# SCH_STM32_V3_3_0_2023-02-14.net
KiCad netlist of a schematic drawn in EasyEDA
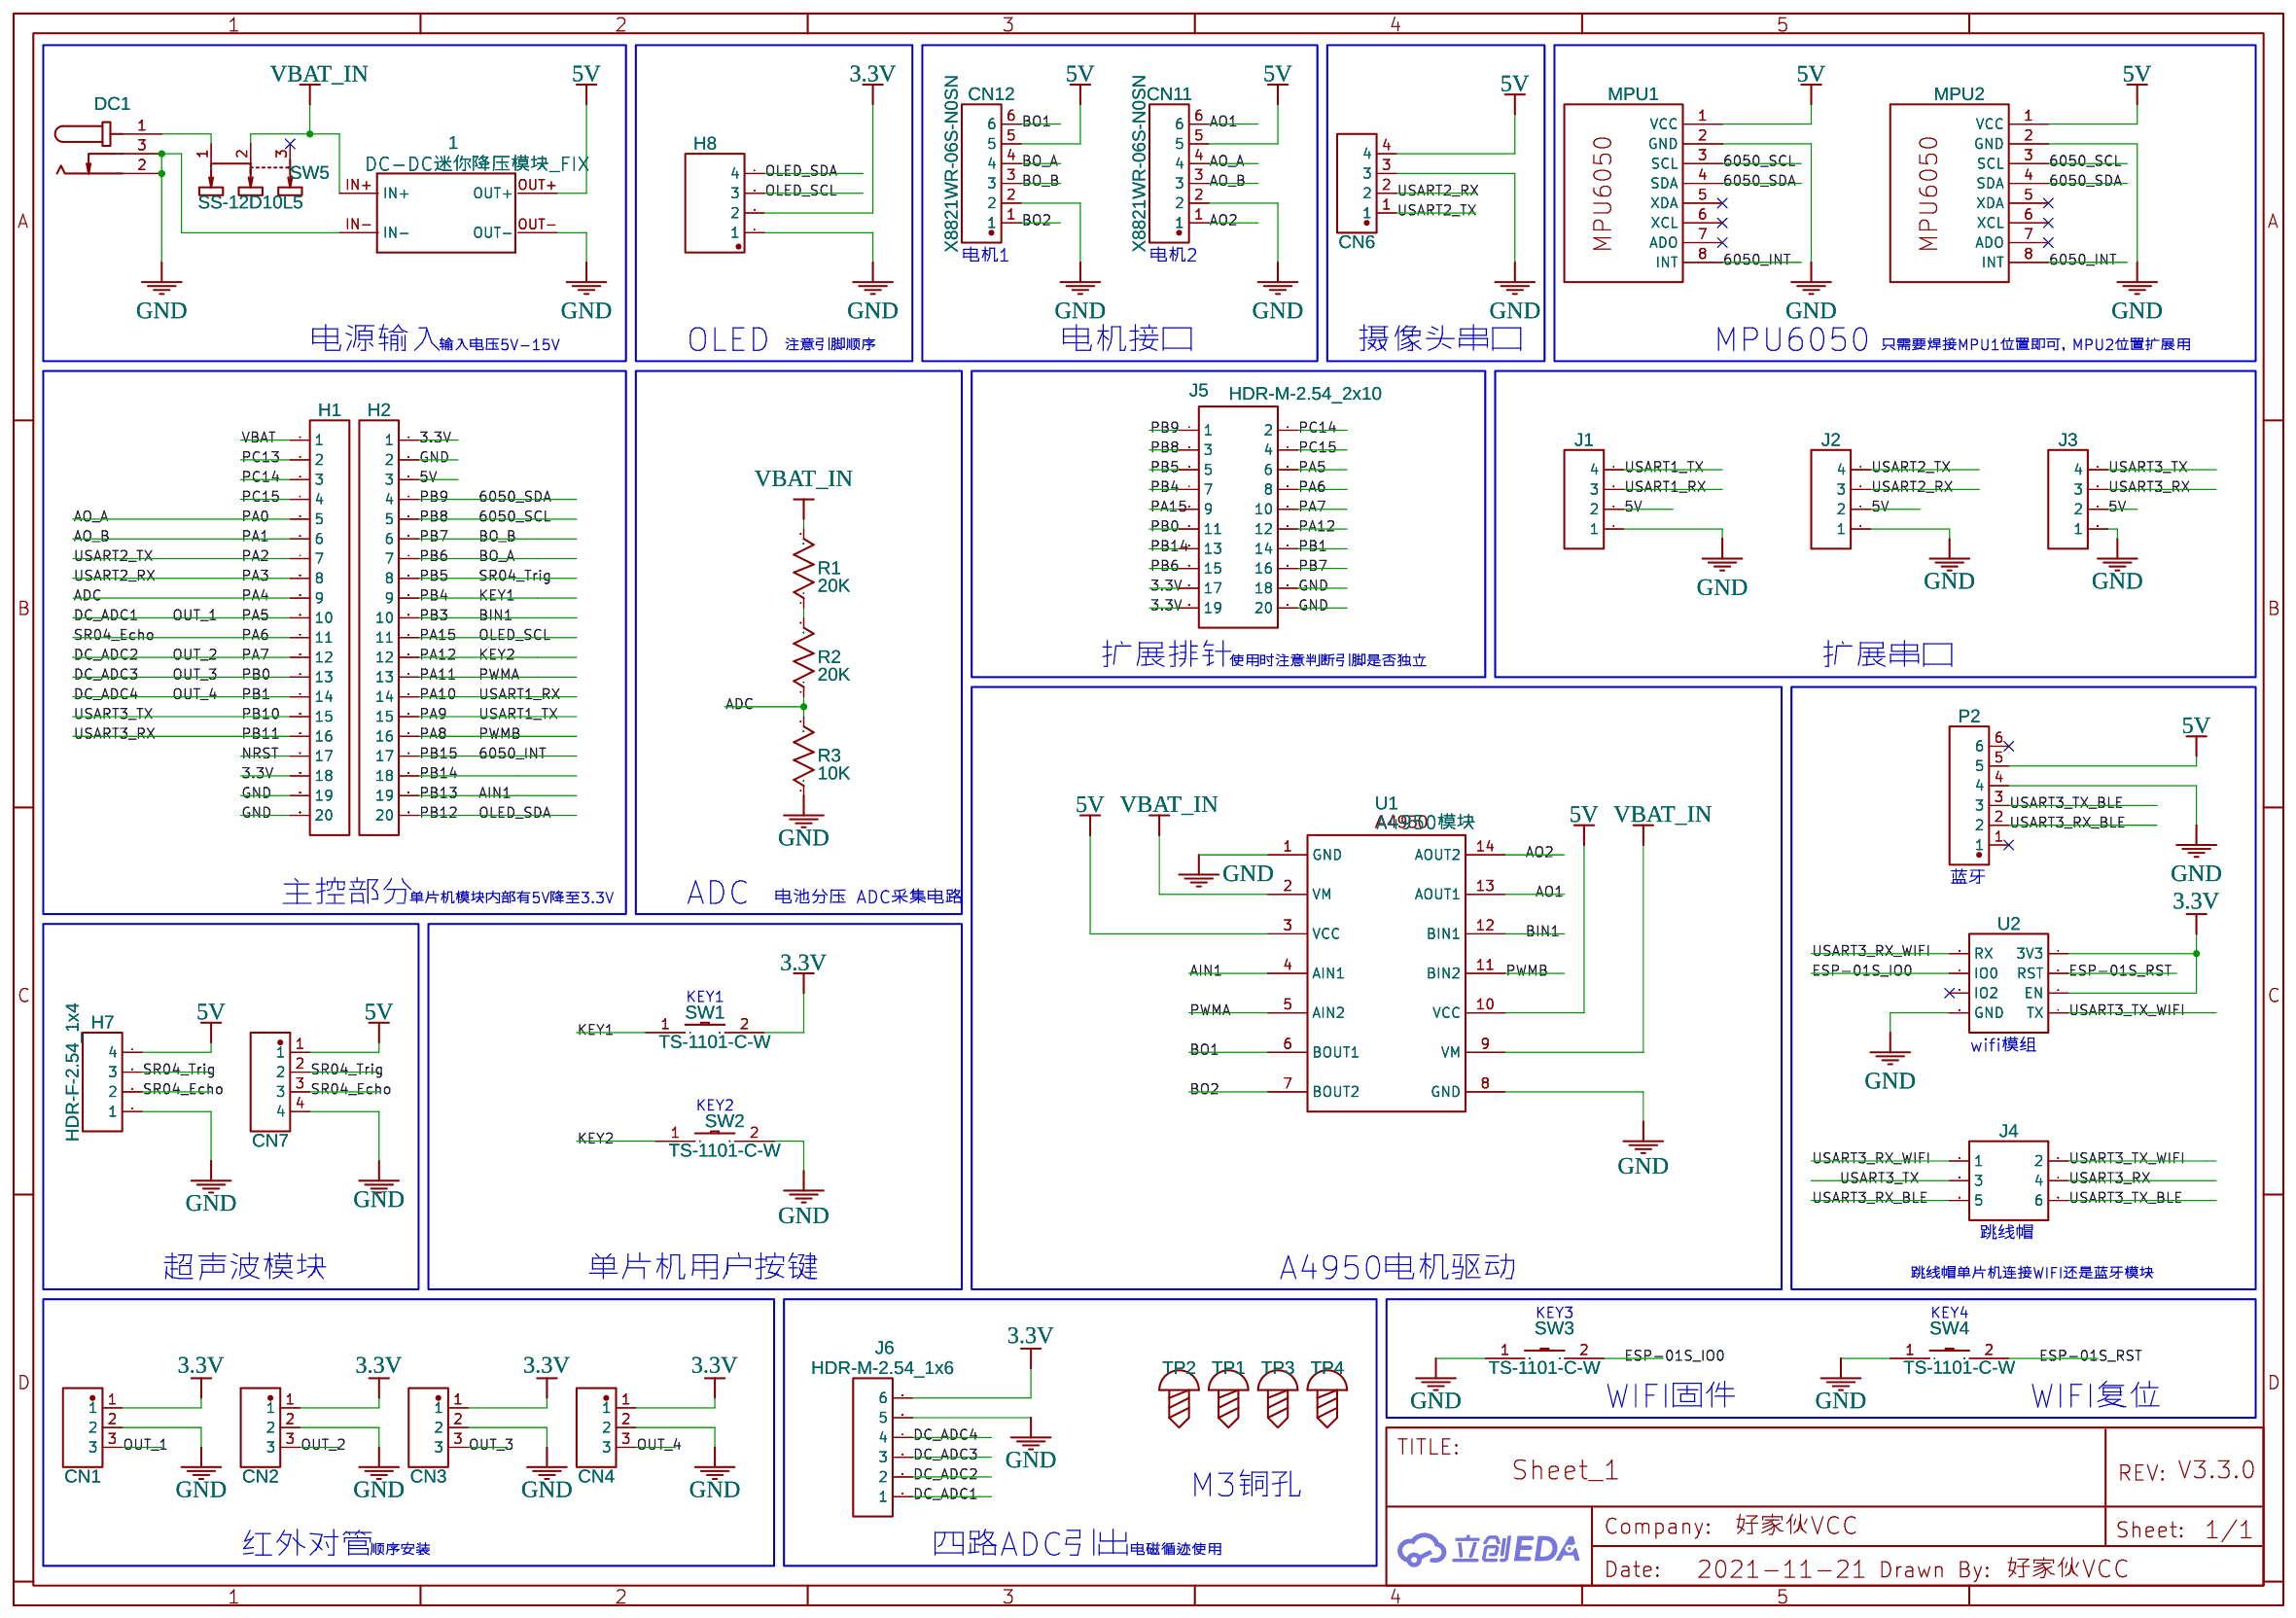
[diagram p0: schematic sheet]

(export (version "E")
  (design (tool "Eeschema 10.0.6"))
  (components
    (comp (ref "1") (value "DC-DC迷你降压模块_FIX") (libsource (lib "") (part "DC-DC迷你降压模块_FIX")))
    (comp (ref "CN1")
      (value "X8821WR-03S-N0SN")
      (fields (field (name "BOM_Supplier Part") "C388740"))
      (libsource (lib "") (part "X8821WR-03S-N0SN"))
    )
    (comp (ref "CN2")
      (value "X8821WR-03S-N0SN")
      (fields (field (name "BOM_Supplier Part") "C388740"))
      (libsource (lib "") (part "X8821WR-03S-N0SN"))
    )
    (comp (ref "CN3")
      (value "X8821WR-03S-N0SN")
      (fields (field (name "BOM_Supplier Part") "C388740"))
      (libsource (lib "") (part "X8821WR-03S-N0SN"))
    )
    (comp (ref "CN4")
      (value "X8821WR-03S-N0SN")
      (fields (field (name "BOM_Supplier Part") "C388740"))
      (libsource (lib "") (part "X8821WR-03S-N0SN"))
    )
    (comp (ref "CN6")
      (value "HX25003-4WAP")
      (fields (field (name "BOM_Supplier Part") "C442328"))
      (libsource (lib "") (part "HX25003-4WAP_1"))
    )
    (comp (ref "CN7")
      (value "HX25003-4WAP")
      (fields (field (name "BOM_Supplier Part") "C442328"))
      (libsource (lib "") (part "HX25003-4WAP"))
    )
    (comp (ref "CN11")
      (value "X8821WR-06S-N0SN")
      (fields (field (name "BOM_Supplier Part") "C388743"))
      (libsource (lib "") (part "X8821WR-06S-N0SN"))
    )
    (comp (ref "CN12")
      (value "X8821WR-06S-N0SN")
      (fields (field (name "BOM_Supplier Part") "C388743"))
      (libsource (lib "") (part "X8821WR-06S-N0SN"))
    )
    (comp (ref "DC1")
      (value "DC005_C431533")
      (fields (field (name "BOM_Manufacturer Part") "DC005") (field (name "BOM_Supplier Part") "C431533"))
      (libsource (lib "") (part "DC005_C431533"))
    )
    (comp (ref "H1")
      (value "HDR-F-2.54_1x20")
      (fields
        (field (name "BOM_Manufacturer Part") "2.54mm 1*20P Female header")
        (field (name "BOM_Supplier Part") "C50984")
      )
      (libsource (lib "") (part "HDR-F-2.54_1x20_1"))
    )
    (comp (ref "H2")
      (value "HDR-F-2.54_1x20")
      (fields
        (field (name "BOM_Manufacturer Part") "2.54mm 1*20P Female header")
        (field (name "BOM_Supplier Part") "C50984")
      )
      (libsource (lib "") (part "HDR-F-2.54_1x20"))
    )
    (comp (ref "H7")
      (value "HDR-F-2.54_1x4")
      (fields (field (name "BOM_Supplier Part") "C225501"))
      (libsource (lib "") (part "HDR-F-2.54_1x4"))
    )
    (comp (ref "H8")
      (value "Header-Male-2.54_1x4")
      (fields
        (field (name "BOM_Manufacturer Part") "A2541HWV-4P")
        (field (name "BOM_Supplier Part") "C225501")
      )
      (libsource (lib "") (part "Header-Male-2.54_1x4"))
    )
    (comp (ref "J1")
      (value "HDR-M-2.54_1x4")
      (fields (field (name "BOM_Supplier Part") "C124378"))
      (libsource (lib "") (part "HDR-M-2.54_1x4"))
    )
    (comp (ref "J2")
      (value "HDR-M-2.54_1x4")
      (fields (field (name "BOM_Supplier Part") "C124378"))
      (libsource (lib "") (part "HDR-M-2.54_1x4"))
    )
    (comp (ref "J3")
      (value "HDR-M-2.54_1x4")
      (fields (field (name "BOM_Supplier Part") "C124378"))
      (libsource (lib "") (part "HDR-M-2.54_1x4"))
    )
    (comp (ref "J4")
      (value "Header-Male-2.54_2x3")
      (fields (field (name "BOM_Supplier Part") "C65114"))
      (libsource (lib "") (part "Header-Male-2.54_2x3"))
    )
    (comp (ref "J5")
      (value "HDR-M-2.54_2x10")
      (fields (field (name "BOM_Supplier Part") "C124359"))
      (libsource (lib "") (part "HDR-M-2.54_2x10"))
    )
    (comp (ref "J6")
      (value "HDR-M-2.54_1x6")
      (fields (field (name "BOM_Supplier Part") "C190819"))
      (libsource (lib "") (part "HDR-M-2.54_1x6"))
    )
    (comp (ref "MPU1") (value "MPU6050 有孔(锁定丝印)") (libsource (lib "") (part "MPU6050 有孔(锁定丝印)")))
    (comp (ref "MPU2") (value "MPU6050 有孔(锁定丝印)") (libsource (lib "") (part "MPU6050 有孔(锁定丝印)")))
    (comp (ref "P2")
      (value "Header-Female-2.54_1x6")
      (fields
        (field (name "BOM_Manufacturer Part") "Female header 1*6p")
        (field (name "BOM_Supplier Part") "C40877")
      )
      (libsource (lib "") (part "Header-Female-2.54_1x6"))
    )
    (comp (ref "R1") (value "20K") (libsource (lib "") (part "R_0603_US")))
    (comp (ref "R2") (value "20K") (libsource (lib "") (part "R_0603_US")))
    (comp (ref "R3") (value "10K") (libsource (lib "") (part "R_0603_US")))
    (comp (ref "SW1")
      (value "TS-1101-C-W")
      (fields (field (name "BOM_Supplier Part") "C318938"))
      (libsource (lib "") (part "TS-1101-C-W"))
    )
    (comp (ref "SW2")
      (value "TS-1101-C-W")
      (fields (field (name "BOM_Supplier Part") "C318938"))
      (libsource (lib "") (part "TS-1101-C-W"))
    )
    (comp (ref "SW3")
      (value "TS-1101-C-W")
      (fields (field (name "BOM_Supplier Part") "C318938"))
      (libsource (lib "") (part "TS-1101-C-W"))
    )
    (comp (ref "SW4")
      (value "TS-1101-C-W")
      (fields (field (name "BOM_Supplier Part") "C318938"))
      (libsource (lib "") (part "TS-1101-C-W"))
    )
    (comp (ref "SW5")
      (value "SS-12D10L5")
      (fields (field (name "BOM_Supplier Part") "C319012"))
      (libsource (lib "") (part "SS-12D10L5"))
    )
    (comp (ref "TP1") (value "M3铜柱带丝印") (libsource (lib "") (part "M3铜柱带丝印")))
    (comp (ref "TP2") (value "M3铜柱带丝印") (libsource (lib "") (part "M3铜柱带丝印")))
    (comp (ref "TP3") (value "M3铜柱带丝印") (libsource (lib "") (part "M3铜柱带丝印")))
    (comp (ref "TP4") (value "M3铜柱带丝印") (libsource (lib "") (part "M3铜柱带丝印")))
    (comp (ref "U1") (value "A4950模块") (libsource (lib "") (part "A4950模块")))
    (comp (ref "U2") (value "ESP-01S模块") (libsource (lib "") (part "ESP-01S模块")))
  )
  (nets
    (net (code "1") (name "/6050_INT") (class "Default")
      (node (ref "H2") (pin "17") (pinfunction "17_17") (pintype "unspecified"))
      (node (ref "MPU1") (pin "8") (pinfunction "INT_8") (pintype "unspecified"))
      (node (ref "MPU2") (pin "8") (pinfunction "INT_8") (pintype "unspecified"))
    )
    (net (code "2") (name "/6050_SCL") (class "Default")
      (node (ref "H2") (pin "5") (pinfunction "5_5") (pintype "unspecified"))
      (node (ref "J5") (pin "3") (pinfunction "3_3") (pintype "unspecified"))
      (node (ref "MPU1") (pin "3") (pinfunction "SCL_3") (pintype "unspecified"))
      (node (ref "MPU2") (pin "3") (pinfunction "SCL_3") (pintype "unspecified"))
    )
    (net (code "3") (name "/6050_SDA") (class "Default")
      (node (ref "H2") (pin "4") (pinfunction "4_4") (pintype "unspecified"))
      (node (ref "J5") (pin "1") (pinfunction "1_1") (pintype "unspecified"))
      (node (ref "MPU1") (pin "4") (pinfunction "SDA_4") (pintype "unspecified"))
      (node (ref "MPU2") (pin "4") (pinfunction "SDA_4") (pintype "unspecified"))
    )
    (net (code "4") (name "/ADC") (class "Default")
      (node (ref "H1") (pin "9") (pinfunction "9_9") (pintype "unspecified"))
      (node (ref "R2") (pin "1") (pinfunction "1_1") (pintype "unspecified"))
      (node (ref "R3") (pin "2") (pinfunction "2_2") (pintype "unspecified"))
    )
    (net (code "5") (name "/AIN1") (class "Default")
      (node (ref "H2") (pin "19") (pinfunction "19_19") (pintype "unspecified"))
      (node (ref "U1") (pin "4") (pinfunction "AIN1_4") (pintype "unspecified"))
    )
    (net (code "6") (name "/AO1") (class "Default")
      (node (ref "CN11") (pin "6") (pinfunction "6_6") (pintype "unspecified"))
      (node (ref "U1") (pin "13") (pinfunction "AOUT1_13") (pintype "unspecified"))
    )
    (net (code "7") (name "/AO2") (class "Default")
      (node (ref "CN11") (pin "1") (pinfunction "1_1") (pintype "unspecified"))
      (node (ref "U1") (pin "14") (pinfunction "AOUT2_14") (pintype "unspecified"))
    )
    (net (code "8") (name "/AO_A") (class "Default")
      (node (ref "CN11") (pin "4") (pinfunction "4_4") (pintype "unspecified"))
      (node (ref "H1") (pin "5") (pinfunction "5_5") (pintype "unspecified"))
    )
    (net (code "9") (name "/AO_B") (class "Default")
      (node (ref "CN11") (pin "3") (pinfunction "3_3") (pintype "unspecified"))
      (node (ref "H1") (pin "6") (pinfunction "6_6") (pintype "unspecified"))
    )
    (net (code "10") (name "/BIN1") (class "Default")
      (node (ref "H2") (pin "10") (pinfunction "10_10") (pintype "unspecified"))
      (node (ref "U1") (pin "12") (pinfunction "BIN1_12") (pintype "unspecified"))
    )
    (net (code "11") (name "/BO1") (class "Default")
      (node (ref "CN12") (pin "6") (pinfunction "6_6") (pintype "unspecified"))
      (node (ref "U1") (pin "6") (pinfunction "BOUT1_6") (pintype "unspecified"))
    )
    (net (code "12") (name "/BO2") (class "Default")
      (node (ref "CN12") (pin "1") (pinfunction "1_1") (pintype "unspecified"))
      (node (ref "U1") (pin "7") (pinfunction "BOUT2_7") (pintype "unspecified"))
    )
    (net (code "13") (name "/BO_A") (class "Default")
      (node (ref "CN12") (pin "4") (pinfunction "4_4") (pintype "unspecified"))
      (node (ref "H2") (pin "7") (pinfunction "7_7") (pintype "unspecified"))
      (node (ref "J5") (pin "15") (pinfunction "15_15") (pintype "unspecified"))
    )
    (net (code "14") (name "/BO_B") (class "Default")
      (node (ref "CN12") (pin "3") (pinfunction "3_3") (pintype "unspecified"))
      (node (ref "H2") (pin "6") (pinfunction "6_6") (pintype "unspecified"))
      (node (ref "J5") (pin "16") (pinfunction "16_16") (pintype "unspecified"))
    )
    (net (code "15") (name "/DC_ADC1") (class "Default")
      (node (ref "CN1") (pin "3") (pinfunction "3_3") (pintype "unspecified"))
      (node (ref "H1") (pin "10") (pinfunction "10_10") (pintype "unspecified"))
      (node (ref "J5") (pin "6") (pinfunction "6_6") (pintype "unspecified"))
      (node (ref "J6") (pin "1") (pinfunction "1_1") (pintype "input"))
    )
    (net (code "16") (name "/DC_ADC2") (class "Default")
      (node (ref "CN2") (pin "3") (pinfunction "3_3") (pintype "unspecified"))
      (node (ref "H1") (pin "12") (pinfunction "12_12") (pintype "unspecified"))
      (node (ref "J5") (pin "10") (pinfunction "10_10") (pintype "unspecified"))
      (node (ref "J6") (pin "2") (pinfunction "2_2") (pintype "input"))
    )
    (net (code "17") (name "/DC_ADC3") (class "Default")
      (node (ref "CN3") (pin "3") (pinfunction "3_3") (pintype "unspecified"))
      (node (ref "H1") (pin "13") (pinfunction "13_13") (pintype "unspecified"))
      (node (ref "J5") (pin "11") (pinfunction "11_11") (pintype "unspecified"))
      (node (ref "J6") (pin "3") (pinfunction "3_3") (pintype "input"))
    )
    (net (code "18") (name "/DC_ADC4") (class "Default")
      (node (ref "CN4") (pin "3") (pinfunction "3_3") (pintype "unspecified"))
      (node (ref "H1") (pin "14") (pinfunction "14_14") (pintype "unspecified"))
      (node (ref "J5") (pin "14") (pinfunction "14_14") (pintype "unspecified"))
      (node (ref "J6") (pin "4") (pinfunction "4_4") (pintype "input"))
    )
    (net (code "19") (name "/ESP-01S_IO0") (class "Default")
      (node (ref "SW3") (pin "2") (pinfunction "2_2") (pintype "unspecified"))
      (node (ref "U2") (pin "7") (pinfunction "IO0_7") (pintype "unspecified"))
    )
    (net (code "20") (name "/ESP-01S_RST") (class "Default")
      (node (ref "SW4") (pin "2") (pinfunction "2_2") (pintype "unspecified"))
      (node (ref "U2") (pin "2") (pinfunction "RST_2") (pintype "unspecified"))
    )
    (net (code "21") (name "/KEY1") (class "Default")
      (node (ref "H2") (pin "9") (pinfunction "9_9") (pintype "unspecified"))
      (node (ref "J5") (pin "7") (pinfunction "7_7") (pintype "unspecified"))
      (node (ref "SW1") (pin "1") (pinfunction "1_1") (pintype "unspecified"))
    )
    (net (code "22") (name "/KEY2") (class "Default")
      (node (ref "H2") (pin "12") (pinfunction "12_12") (pintype "unspecified"))
      (node (ref "J5") (pin "12") (pinfunction "12_12") (pintype "unspecified"))
      (node (ref "SW2") (pin "1") (pinfunction "1_1") (pintype "unspecified"))
    )
    (net (code "23") (name "/NRST") (class "Default")
      (node (ref "H1") (pin "17") (pinfunction "17_17") (pintype "unspecified"))
    )
    (net (code "24") (name "/OLED_SCL") (class "Default")
      (node (ref "H2") (pin "11") (pinfunction "11_11") (pintype "unspecified"))
      (node (ref "H8") (pin "3") (pinfunction "3_3") (pintype "unspecified"))
      (node (ref "J5") (pin "9") (pinfunction "9_9") (pintype "unspecified"))
    )
    (net (code "25") (name "/OLED_SDA") (class "Default")
      (node (ref "H2") (pin "20") (pinfunction "20_20") (pintype "unspecified"))
      (node (ref "H8") (pin "4") (pinfunction "4_4") (pintype "unspecified"))
    )
    (net (code "26") (name "/PA2") (class "Default")
      (node (ref "CN6") (pin "1") (pinfunction "1_1") (pintype "unspecified"))
      (node (ref "H1") (pin "7") (pinfunction "7_7") (pintype "unspecified"))
      (node (ref "J2") (pin "4") (pinfunction "4_4") (pintype "unspecified"))
    )
    (net (code "27") (name "/PA3") (class "Default")
      (node (ref "CN6") (pin "2") (pinfunction "2_2") (pintype "unspecified"))
      (node (ref "H1") (pin "8") (pinfunction "8_8") (pintype "unspecified"))
      (node (ref "J2") (pin "3") (pinfunction "3_3") (pintype "unspecified"))
    )
    (net (code "28") (name "/PA6") (class "Default")
      (node (ref "CN7") (pin "3") (pinfunction "3_3") (pintype "unspecified"))
      (node (ref "H1") (pin "11") (pinfunction "11_11") (pintype "unspecified"))
      (node (ref "H7") (pin "2") (pinfunction "2_2") (pintype "unspecified"))
      (node (ref "J5") (pin "8") (pinfunction "8_8") (pintype "unspecified"))
    )
    (net (code "29") (name "/PA8") (class "Default")
      (node (ref "H2") (pin "16") (pinfunction "16_16") (pintype "unspecified"))
      (node (ref "U1") (pin "11") (pinfunction "BIN2_11") (pintype "unspecified"))
    )
    (net (code "30") (name "/PA9") (class "Default")
      (node (ref "H2") (pin "15") (pinfunction "15_15") (pintype "unspecified"))
      (node (ref "J1") (pin "4") (pinfunction "4_4") (pintype "unspecified"))
    )
    (net (code "31") (name "/PA10") (class "Default")
      (node (ref "H2") (pin "14") (pinfunction "14_14") (pintype "unspecified"))
      (node (ref "J1") (pin "3") (pinfunction "3_3") (pintype "unspecified"))
    )
    (net (code "32") (name "/PA11") (class "Default")
      (node (ref "H2") (pin "13") (pinfunction "13_13") (pintype "unspecified"))
      (node (ref "U1") (pin "5") (pinfunction "AIN2_5") (pintype "unspecified"))
    )
    (net (code "33") (name "/PB5") (class "Default")
      (node (ref "CN7") (pin "2") (pinfunction "2_2") (pintype "unspecified"))
      (node (ref "H2") (pin "8") (pinfunction "8_8") (pintype "unspecified"))
      (node (ref "H7") (pin "3") (pinfunction "3_3") (pintype "unspecified"))
      (node (ref "J5") (pin "5") (pinfunction "5_5") (pintype "unspecified"))
    )
    (net (code "34") (name "/PB10") (class "Default")
      (node (ref "H1") (pin "15") (pinfunction "15_15") (pintype "unspecified"))
      (node (ref "J3") (pin "4") (pinfunction "4_4") (pintype "unspecified"))
      (node (ref "J4") (pin "3") (pinfunction "3_3") (pintype "input"))
    )
    (net (code "35") (name "/PB11") (class "Default")
      (node (ref "H1") (pin "16") (pinfunction "16_16") (pintype "unspecified"))
      (node (ref "J3") (pin "3") (pinfunction "3_3") (pintype "unspecified"))
      (node (ref "J4") (pin "4") (pinfunction "4_4") (pintype "input"))
    )
    (net (code "36") (name "/PB14") (class "Default")
      (node (ref "H2") (pin "18") (pinfunction "18_18") (pintype "unspecified"))
      (node (ref "J5") (pin "13") (pinfunction "13_13") (pintype "unspecified"))
    )
    (net (code "37") (name "/PC13") (class "Default")
      (node (ref "H1") (pin "2") (pinfunction "2_2") (pintype "unspecified"))
    )
    (net (code "38") (name "/PC14") (class "Default")
      (node (ref "H1") (pin "3") (pinfunction "3_3") (pintype "unspecified"))
      (node (ref "J5") (pin "2") (pinfunction "2_2") (pintype "unspecified"))
    )
    (net (code "39") (name "/PC15") (class "Default")
      (node (ref "H1") (pin "4") (pinfunction "4_4") (pintype "unspecified"))
      (node (ref "J5") (pin "4") (pinfunction "4_4") (pintype "unspecified"))
    )
    (net (code "40") (name "/USART3_RX_BLE") (class "Default")
      (node (ref "J4") (pin "5") (pinfunction "5_5") (pintype "input"))
      (node (ref "P2") (pin "2") (pinfunction "2_2") (pintype "unspecified"))
    )
    (net (code "41") (name "/USART3_RX_WIFI") (class "Default")
      (node (ref "J4") (pin "1") (pinfunction "1_1") (pintype "input"))
      (node (ref "U2") (pin "8") (pinfunction "RX_8") (pintype "unspecified"))
    )
    (net (code "42") (name "/USART3_TX_BLE") (class "Default")
      (node (ref "J4") (pin "6") (pinfunction "6_6") (pintype "input"))
      (node (ref "P2") (pin "3") (pinfunction "3_3") (pintype "unspecified"))
    )
    (net (code "43") (name "/USART3_TX_WIFI") (class "Default")
      (node (ref "J4") (pin "2") (pinfunction "2_2") (pintype "input"))
      (node (ref "U2") (pin "4") (pinfunction "TX_4") (pintype "unspecified"))
    )
    (net (code "44") (name "/VBAT") (class "Default")
      (node (ref "H1") (pin "1") (pinfunction "1_1") (pintype "unspecified"))
    )
    (net (code "45") (name "3.3V") (class "Default")
      (node (ref "CN1") (pin "1") (pinfunction "1_1") (pintype "unspecified"))
      (node (ref "CN2") (pin "1") (pinfunction "1_1") (pintype "unspecified"))
      (node (ref "CN3") (pin "1") (pinfunction "1_1") (pintype "unspecified"))
      (node (ref "CN4") (pin "1") (pinfunction "1_1") (pintype "unspecified"))
      (node (ref "H1") (pin "18") (pinfunction "18_18") (pintype "unspecified"))
      (node (ref "H2") (pin "1") (pinfunction "1_1") (pintype "unspecified"))
      (node (ref "H8") (pin "2") (pinfunction "2_2") (pintype "unspecified"))
      (node (ref "J5") (pin "17") (pinfunction "17_17") (pintype "unspecified"))
      (node (ref "J5") (pin "19") (pinfunction "19_19") (pintype "unspecified"))
      (node (ref "J6") (pin "6") (pinfunction "6_6") (pintype "input"))
      (node (ref "SW1") (pin "2") (pinfunction "2_2") (pintype "unspecified"))
      (node (ref "U2") (pin "1") (pinfunction "3V3_1") (pintype "unspecified"))
      (node (ref "U2") (pin "3") (pinfunction "EN_3") (pintype "unspecified"))
    )
    (net (code "46") (name "5V") (class "Default")
      (node (ref "1") (pin "OUT+") (pinfunction "OUT+_OUT+") (pintype "bidirectional"))
      (node (ref "CN11") (pin "5") (pinfunction "5_5") (pintype "unspecified"))
      (node (ref "CN12") (pin "5") (pinfunction "5_5") (pintype "unspecified"))
      (node (ref "CN6") (pin "4") (pinfunction "4_4") (pintype "unspecified"))
      (node (ref "CN7") (pin "1") (pinfunction "1_1") (pintype "unspecified"))
      (node (ref "H2") (pin "3") (pinfunction "3_3") (pintype "unspecified"))
      (node (ref "H7") (pin "4") (pinfunction "4_4") (pintype "unspecified"))
      (node (ref "J1") (pin "2") (pinfunction "2_2") (pintype "unspecified"))
      (node (ref "J2") (pin "2") (pinfunction "2_2") (pintype "unspecified"))
      (node (ref "J3") (pin "2") (pinfunction "2_2") (pintype "unspecified"))
      (node (ref "MPU1") (pin "1") (pinfunction "VCC_1") (pintype "unspecified"))
      (node (ref "MPU2") (pin "1") (pinfunction "VCC_1") (pintype "unspecified"))
      (node (ref "P2") (pin "5") (pinfunction "5_5") (pintype "unspecified"))
      (node (ref "U1") (pin "10") (pinfunction "VCC_10") (pintype "unspecified"))
      (node (ref "U1") (pin "3") (pinfunction "VCC_3") (pintype "unspecified"))
    )
    (net (code "47") (name "GND") (class "Default")
      (node (ref "1") (pin "IN-") (pinfunction "IN-_IN-") (pintype "bidirectional"))
      (node (ref "1") (pin "OUT-") (pinfunction "OUT-_OUT-") (pintype "bidirectional"))
      (node (ref "CN1") (pin "2") (pinfunction "2_2") (pintype "unspecified"))
      (node (ref "CN11") (pin "2") (pinfunction "2_2") (pintype "unspecified"))
      (node (ref "CN12") (pin "2") (pinfunction "2_2") (pintype "unspecified"))
      (node (ref "CN2") (pin "2") (pinfunction "2_2") (pintype "unspecified"))
      (node (ref "CN3") (pin "2") (pinfunction "2_2") (pintype "unspecified"))
      (node (ref "CN4") (pin "2") (pinfunction "2_2") (pintype "unspecified"))
      (node (ref "CN6") (pin "3") (pinfunction "3_3") (pintype "unspecified"))
      (node (ref "CN7") (pin "4") (pinfunction "4_4") (pintype "unspecified"))
      (node (ref "DC1") (pin "2") (pinfunction "2_2") (pintype "unspecified"))
      (node (ref "DC1") (pin "3") (pinfunction "3_3") (pintype "unspecified"))
      (node (ref "H1") (pin "19") (pinfunction "19_19") (pintype "unspecified"))
      (node (ref "H1") (pin "20") (pinfunction "20_20") (pintype "unspecified"))
      (node (ref "H2") (pin "2") (pinfunction "2_2") (pintype "unspecified"))
      (node (ref "H7") (pin "1") (pinfunction "1_1") (pintype "unspecified"))
      (node (ref "H8") (pin "1") (pinfunction "1_1") (pintype "unspecified"))
      (node (ref "J1") (pin "1") (pinfunction "1_1") (pintype "unspecified"))
      (node (ref "J2") (pin "1") (pinfunction "1_1") (pintype "unspecified"))
      (node (ref "J3") (pin "1") (pinfunction "1_1") (pintype "unspecified"))
      (node (ref "J5") (pin "18") (pinfunction "18_18") (pintype "unspecified"))
      (node (ref "J5") (pin "20") (pinfunction "20_20") (pintype "unspecified"))
      (node (ref "J6") (pin "5") (pinfunction "5_5") (pintype "input"))
      (node (ref "MPU1") (pin "2") (pinfunction "GND_2") (pintype "unspecified"))
      (node (ref "MPU2") (pin "2") (pinfunction "GND_2") (pintype "unspecified"))
      (node (ref "P2") (pin "4") (pinfunction "4_4") (pintype "unspecified"))
      (node (ref "R3") (pin "1") (pinfunction "1_1") (pintype "unspecified"))
      (node (ref "SW2") (pin "2") (pinfunction "2_2") (pintype "unspecified"))
      (node (ref "SW3") (pin "1") (pinfunction "1_1") (pintype "unspecified"))
      (node (ref "SW4") (pin "1") (pinfunction "1_1") (pintype "unspecified"))
      (node (ref "U1") (pin "1") (pinfunction "GND_1") (pintype "unspecified"))
      (node (ref "U1") (pin "8") (pinfunction "GND_8") (pintype "unspecified"))
      (node (ref "U2") (pin "5") (pinfunction "GND_5") (pintype "unspecified"))
    )
    (net (code "48") (name "Net-(DC1-Pad1)") (class "Default")
      (node (ref "DC1") (pin "1") (pinfunction "1_1") (pintype "unspecified"))
      (node (ref "SW5") (pin "1") (pinfunction "1_1") (pintype "unspecified"))
    )
    (net (code "49") (name "Net-(R1-Pad1)") (class "Default")
      (node (ref "R1") (pin "1") (pinfunction "1_1") (pintype "unspecified"))
      (node (ref "R2") (pin "2") (pinfunction "2_2") (pintype "unspecified"))
    )
    (net (code "50") (name "VBAT_IN") (class "Default")
      (node (ref "1") (pin "IN+") (pinfunction "IN+_IN+") (pintype "bidirectional"))
      (node (ref "R1") (pin "2") (pinfunction "2_2") (pintype "unspecified"))
      (node (ref "SW5") (pin "2") (pinfunction "2_2") (pintype "unspecified"))
      (node (ref "U1") (pin "2") (pinfunction "VM_2") (pintype "unspecified"))
      (node (ref "U1") (pin "9") (pinfunction "VM_9") (pintype "unspecified"))
    )
    (net (code "51") (name "unconnected-(MPU1-ADO-Pad7)") (class "Default")
      (node (ref "MPU1") (pin "7") (pinfunction "ADO_7") (pintype "unspecified+no_connect"))
    )
    (net (code "52") (name "unconnected-(MPU1-XCL-Pad6)") (class "Default")
      (node (ref "MPU1") (pin "6") (pinfunction "XCL_6") (pintype "unspecified+no_connect"))
    )
    (net (code "53") (name "unconnected-(MPU1-XDA-Pad5)") (class "Default")
      (node (ref "MPU1") (pin "5") (pinfunction "XDA_5") (pintype "unspecified+no_connect"))
    )
    (net (code "54") (name "unconnected-(MPU2-ADO-Pad7)") (class "Default")
      (node (ref "MPU2") (pin "7") (pinfunction "ADO_7") (pintype "unspecified+no_connect"))
    )
    (net (code "55") (name "unconnected-(MPU2-XCL-Pad6)") (class "Default")
      (node (ref "MPU2") (pin "6") (pinfunction "XCL_6") (pintype "unspecified+no_connect"))
    )
    (net (code "56") (name "unconnected-(MPU2-XDA-Pad5)") (class "Default")
      (node (ref "MPU2") (pin "5") (pinfunction "XDA_5") (pintype "unspecified+no_connect"))
    )
    (net (code "57") (name "unconnected-(P2-Pad1)") (class "Default")
      (node (ref "P2") (pin "1") (pinfunction "1_1") (pintype "unspecified+no_connect"))
    )
    (net (code "58") (name "unconnected-(P2-Pad6)") (class "Default")
      (node (ref "P2") (pin "6") (pinfunction "6_6") (pintype "unspecified+no_connect"))
    )
    (net (code "59") (name "unconnected-(SW5-Pad3)") (class "Default")
      (node (ref "SW5") (pin "3") (pinfunction "3_3") (pintype "unspecified+no_connect"))
    )
    (net (code "60") (name "unconnected-(U2-IO2-Pad6)") (class "Default")
      (node (ref "U2") (pin "6") (pinfunction "IO2_6") (pintype "unspecified+no_connect"))
    )
  )
)
